# Copy_of_Bramka_Main.net
KiCad netlist of a schematic drawn in Altium Designer
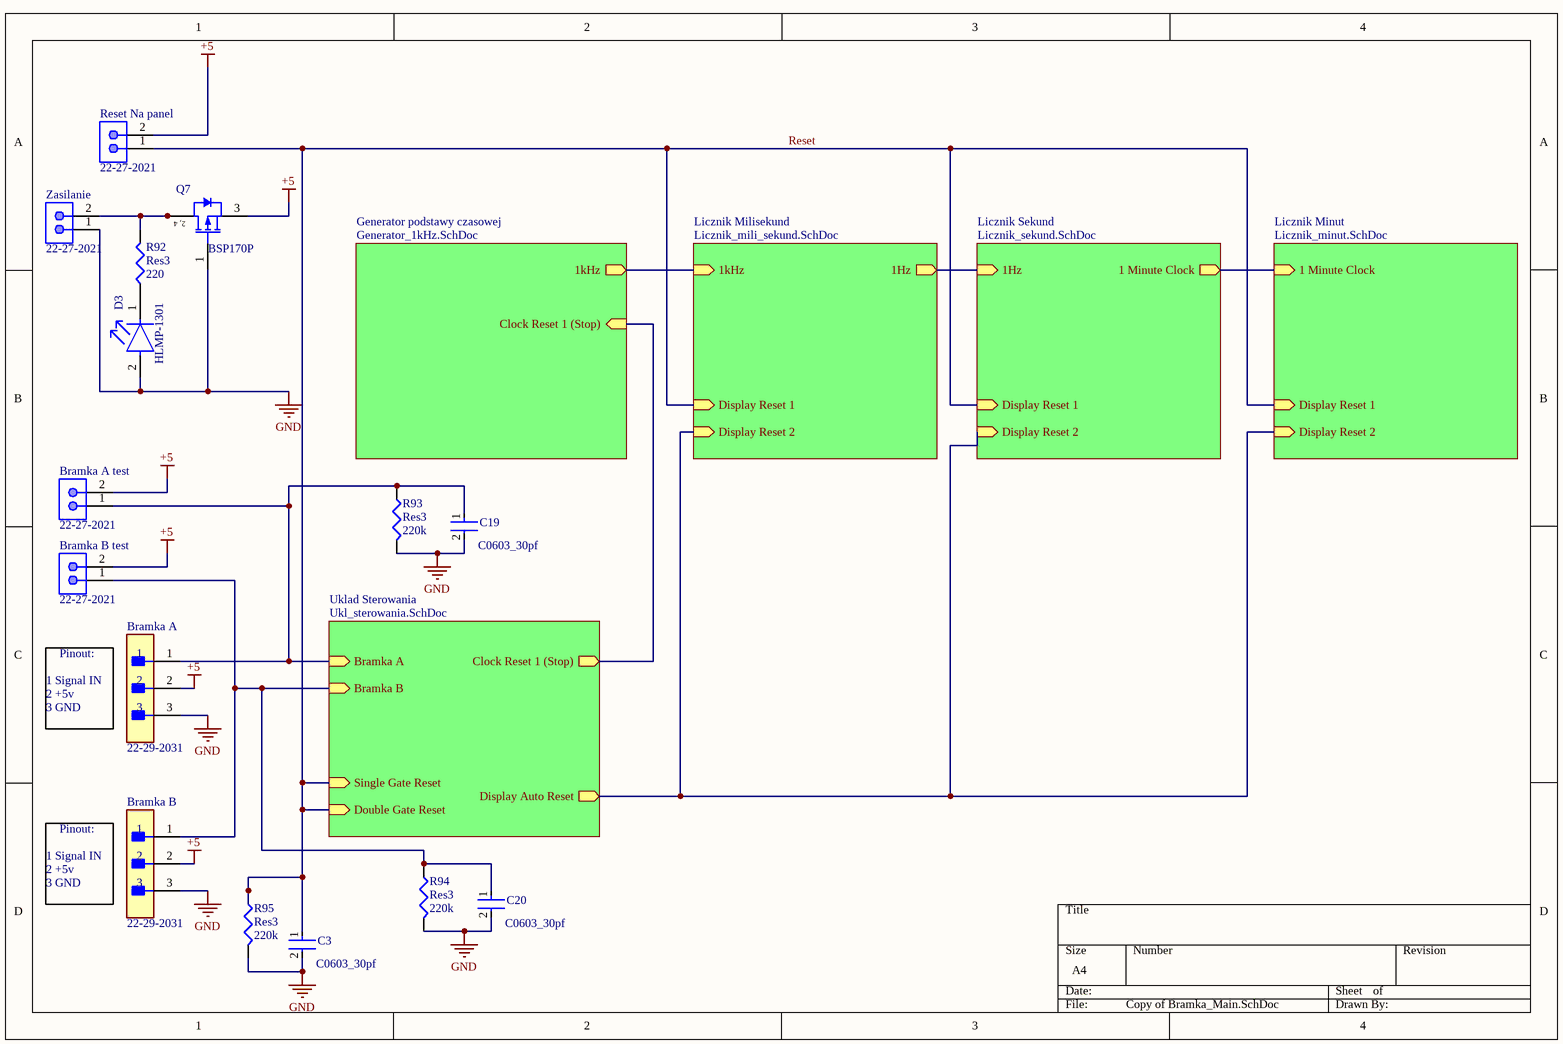
[diagram p0: Copy of Bramka_Main.SchDoc]

(export (version "E")
  (design (tool "Eeschema 10.0.6"))
  (components
    (comp (ref "Bramka A")
      (value "22-29-2031")
      (footprint "FP-22-29-2031-MFG")
      (description "CONN HEADER VERT 3POS 2.54MM")
      (libsource (lib "Altium Content Vault") (part "0d3f023dd272f625e17a2be33dea85f"))
    )
    (comp (ref "Bramka A test")
      (value "22-27-2021")
      (footprint "MOLX-22-27-2021_V")
      (fields (field (name "MANUFACTURER") "Molex") (field (name "PARTNUMBER") "0022272021"))
      (libsource (lib "Altium Content Vault") (part "CN-1P-M-R2"))
    )
    (comp (ref "Bramka B")
      (value "22-29-2031")
      (footprint "FP-22-29-2031-MFG")
      (description "CONN HEADER VERT 3POS 2.54MM")
      (libsource (lib "Altium Content Vault") (part "0d3f023dd272f625e17a2be33dea85f"))
    )
    (comp (ref "Bramka B test")
      (value "22-27-2021")
      (footprint "MOLX-22-27-2021_V")
      (fields (field (name "MANUFACTURER") "Molex") (field (name "PARTNUMBER") "0022272021"))
      (libsource (lib "Altium Content Vault") (part "CN-1P-M-R2"))
    )
    (comp (ref "C3")
      (value "C0603_30pf")
      (footprint "FP-C0603C-CF-MFG")
      (description "CAP CER 30PF 50V 5% NP0 0603")
      (fields
        (field (name "MANUFACTURER PART NUMBER") "C0603C300J5GACTU")
        (field (name "MANUFACTURER") "KEMET")
      )
      (libsource (lib "Altium Content Vault") (part "b4654b650e69147ec39a6b967a45e02"))
    )
    (comp (ref "C19")
      (value "C0603_30pf")
      (footprint "FP-C0603C-CF-MFG")
      (description "CAP CER 30PF 50V 5% NP0 0603")
      (fields
        (field (name "MANUFACTURER PART NUMBER") "C0603C300J5GACTU")
        (field (name "MANUFACTURER") "KEMET")
      )
      (libsource (lib "Altium Content Vault") (part "b4654b650e69147ec39a6b967a45e02"))
    )
    (comp (ref "C20")
      (value "C0603_30pf")
      (footprint "FP-C0603C-CF-MFG")
      (description "CAP CER 30PF 50V 5% NP0 0603")
      (fields
        (field (name "MANUFACTURER PART NUMBER") "C0603C300J5GACTU")
        (field (name "MANUFACTURER") "KEMET")
      )
      (libsource (lib "Altium Content Vault") (part "b4654b650e69147ec39a6b967a45e02"))
    )
    (comp (ref "D3")
      (value "HLMP-1301")
      (footprint "FP-HLMP-1301-MFG")
      (description "LED RED DIFFUSED T-1 T/H")
      (fields
        (field (name "OCTOPART") "https://octopart.com/hlmp-1301-broadcom-71130345")
        (field (name "MANUFACTURER") "Broadcom")
      )
      (libsource (lib "Altium Content Vault") (part "8706943c75ba83719d021d2fdc84c58"))
    )
    (comp (ref "Q7")
      (value "BSP170P")
      (footprint "INF-PG-SOT223_SC-73_N")
      (fields (field (name "MANUFACTURER") "Infineon"))
      (libsource (lib "Altium Content Vault") (part "INF-PEMOS-GDSD-4-A"))
    )
    (comp (ref "R92")
      (value "Res3")
      (footprint "6-0805_M")
      (description "Resistor")
      (fields (field (name "ALTIUM_VALUE") "220") (field (name "PUBLISHER") "Altium Limited"))
      (libsource (lib "Miscellaneous Devices") (part "Res3"))
    )
    (comp (ref "R93")
      (value "Res3")
      (footprint "J1-0603")
      (description "Resistor")
      (fields (field (name "ALTIUM_VALUE") "220k") (field (name "PUBLISHER") "Altium Limited"))
      (libsource (lib "Miscellaneous Devices") (part "Res3"))
    )
    (comp (ref "R94")
      (value "Res3")
      (footprint "J1-0603")
      (description "Resistor")
      (fields (field (name "ALTIUM_VALUE") "220k") (field (name "PUBLISHER") "Altium Limited"))
      (libsource (lib "Miscellaneous Devices") (part "Res3"))
    )
    (comp (ref "R95")
      (value "Res3")
      (footprint "J1-0603")
      (description "Resistor")
      (fields (field (name "ALTIUM_VALUE") "220k") (field (name "PUBLISHER") "Altium Limited"))
      (libsource (lib "Miscellaneous Devices") (part "Res3"))
    )
    (comp (ref "Reset Na panel")
      (value "22-27-2021")
      (footprint "MOLX-22-27-2021_V")
      (fields (field (name "MANUFACTURER") "Molex") (field (name "PARTNUMBER") "0022272021"))
      (libsource (lib "Altium Content Vault") (part "CN-1P-M-R2"))
    )
    (comp (ref "Zasilanie")
      (value "22-27-2021")
      (footprint "MOLX-22-27-2021_V")
      (fields (field (name "MANUFACTURER") "Molex") (field (name "PARTNUMBER") "0022272021"))
      (libsource (lib "Altium Content Vault") (part "CN-1P-M-R2"))
    )
  )
  (nets
    (net (code "1") (name "+5") (class "Default")
      (node (ref "Bramka A") (pin "2") (pinfunction "2_2") (pintype "passive"))
      (node (ref "Bramka A test") (pin "2") (pinfunction "2_2") (pintype "passive"))
      (node (ref "Bramka B") (pin "2") (pinfunction "2_2") (pintype "passive"))
      (node (ref "Bramka B test") (pin "2") (pinfunction "2_2") (pintype "passive"))
      (node (ref "Q7") (pin "3") (pinfunction "SOURCE_3") (pintype "passive"))
      (node (ref "Reset Na panel") (pin "2") (pinfunction "2_2") (pintype "passive"))
    )
    (net (code "5") (name "/Bramka A") (class "Default")
      (node (ref "Bramka A") (pin "1") (pinfunction "1_1") (pintype "passive"))
      (node (ref "Bramka A test") (pin "1") (pinfunction "1_1") (pintype "passive"))
      (node (ref "C19") (pin "1") (pinfunction "1_1") (pintype "passive"))
      (node (ref "R93") (pin "1") (pinfunction "1_1") (pintype "passive"))
    )
    (net (code "6") (name "/Bramka B") (class "Default")
      (node (ref "Bramka B") (pin "1") (pinfunction "1_1") (pintype "passive"))
      (node (ref "Bramka B test") (pin "1") (pinfunction "1_1") (pintype "passive"))
      (node (ref "C20") (pin "1") (pinfunction "1_1") (pintype "passive"))
      (node (ref "R94") (pin "1") (pinfunction "1_1") (pintype "passive"))
    )
    (net (code "9") (name "/Reset") (class "Default")
      (node (ref "C3") (pin "1") (pinfunction "1_1") (pintype "passive"))
      (node (ref "R95") (pin "1") (pinfunction "1_1") (pintype "passive"))
      (node (ref "Reset Na panel") (pin "1") (pinfunction "1_1") (pintype "passive"))
    )
    (net (code "10") (name "GND") (class "Default")
      (node (ref "Bramka A") (pin "3") (pinfunction "3_3") (pintype "passive"))
      (node (ref "Bramka B") (pin "3") (pinfunction "3_3") (pintype "passive"))
      (node (ref "C19") (pin "2") (pinfunction "2_2") (pintype "passive"))
      (node (ref "C20") (pin "2") (pinfunction "2_2") (pintype "passive"))
      (node (ref "C3") (pin "2") (pinfunction "2_2") (pintype "passive"))
      (node (ref "D3") (pin "2") (pinfunction "A_2") (pintype "passive"))
      (node (ref "Q7") (pin "1") (pinfunction "GATE_1") (pintype "passive"))
      (node (ref "R93") (pin "2") (pinfunction "2_2") (pintype "passive"))
      (node (ref "R94") (pin "2") (pinfunction "2_2") (pintype "passive"))
      (node (ref "R95") (pin "2") (pinfunction "2_2") (pintype "passive"))
      (node (ref "Zasilanie") (pin "1") (pinfunction "1_1") (pintype "passive"))
    )
    (net (code "11") (name "Net-(D3-C)") (class "Default")
      (node (ref "D3") (pin "1") (pinfunction "C_1") (pintype "passive"))
      (node (ref "R92") (pin "1") (pinfunction "1_1") (pintype "passive"))
    )
    (net (code "12") (name "Net-(Q7-DRAIN-Pad2)") (class "Default")
      (node (ref "Q7") (pin "2") (pinfunction "DRAIN_2") (pintype "passive"))
      (node (ref "Q7") (pin "4") (pinfunction "DRAIN_4") (pintype "passive"))
      (node (ref "R92") (pin "2") (pinfunction "2_2") (pintype "passive"))
      (node (ref "Zasilanie") (pin "2") (pinfunction "2_2") (pintype "passive"))
    )
  )
)
